# BrewPi_Fuscus_Board.net
KiCad netlist of a schematic drawn in EAGLE
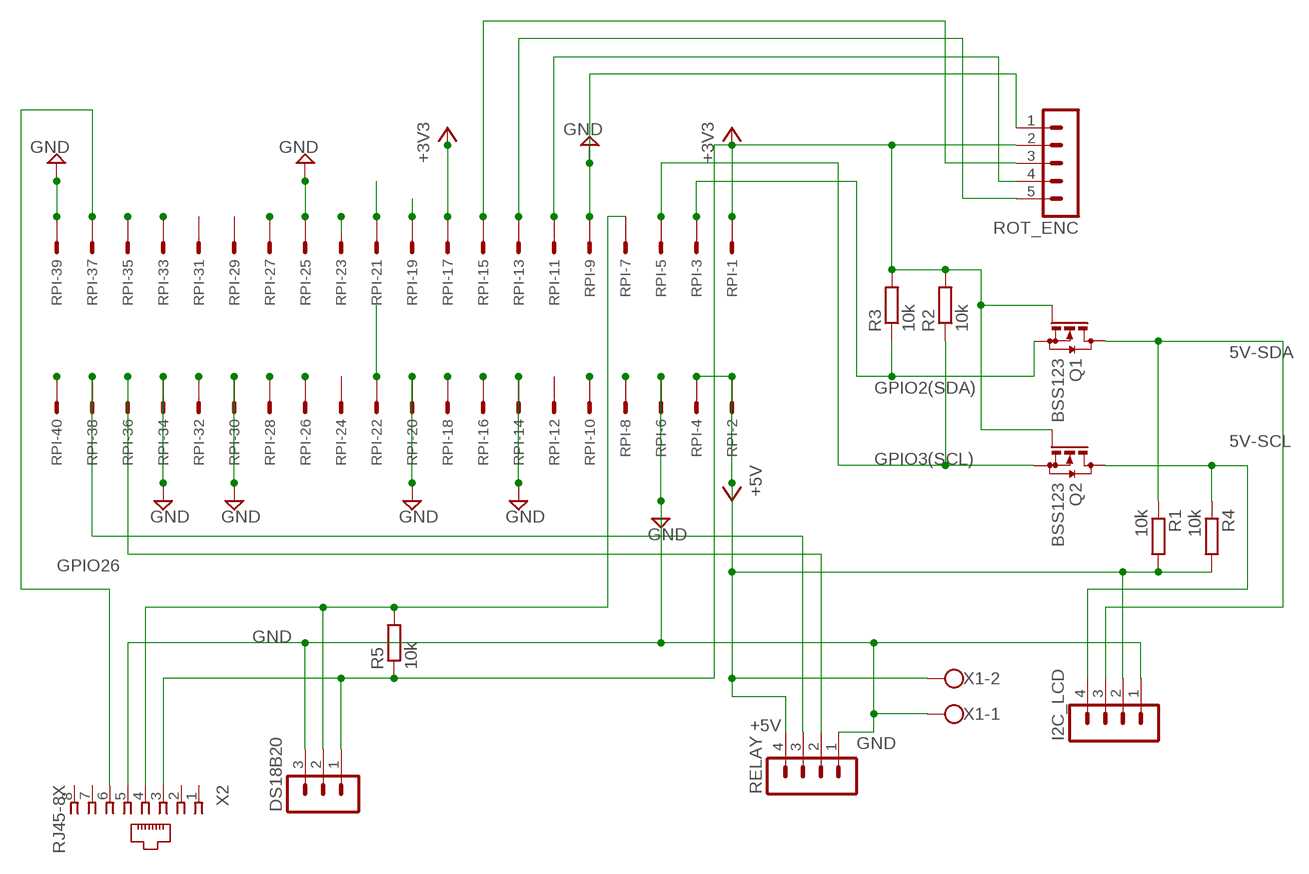
[diagram p0: schematic, sheet 1]

(export (version "E")
  (design (tool "Eeschema 10.0.6"))
  (components
    (comp (ref "DS18B20")
      (value "MA03-1")
      (footprint "eagle-import:MA03-1")
      (libsource (lib "eagle-import") (part "MA03-1"))
    )
    (comp (ref "I2C_LCD")
      (value "MA04-1")
      (footprint "eagle-import:MA04-1")
      (libsource (lib "eagle-import") (part "MA04-1"))
    )
    (comp (ref "Q1")
      (value "BSS123")
      (footprint "eagle-import:SOT23")
      (libsource (lib "eagle-import") (part "BSS123"))
    )
    (comp (ref "Q2")
      (value "BSS123")
      (footprint "eagle-import:SOT23")
      (libsource (lib "eagle-import") (part "BSS123"))
    )
    (comp (ref "R1")
      (value "10k")
      (footprint "eagle-import:M1206")
      (libsource (lib "eagle-import") (part "R-EU_M1206"))
    )
    (comp (ref "R2")
      (value "10k")
      (footprint "eagle-import:M1206")
      (libsource (lib "eagle-import") (part "R-EU_M1206"))
    )
    (comp (ref "R3")
      (value "10k")
      (footprint "eagle-import:M1206")
      (libsource (lib "eagle-import") (part "R-EU_M1206"))
    )
    (comp (ref "R4")
      (value "10k")
      (footprint "eagle-import:M1206")
      (libsource (lib "eagle-import") (part "R-EU_M1206"))
    )
    (comp (ref "R5")
      (value "10k")
      (footprint "eagle-import:M1206")
      (libsource (lib "eagle-import") (part "R-EU_M1206"))
    )
    (comp (ref "RELAY")
      (value "MA04-1")
      (footprint "eagle-import:MA04-1")
      (libsource (lib "eagle-import") (part "MA04-1"))
    )
    (comp (ref "ROT_ENC")
      (value "MA05-1")
      (footprint "eagle-import:MA05-1")
      (libsource (lib "eagle-import") (part "MA05-1"))
    )
    (comp (ref "RPI")
      (value "057-040-1")
      (footprint "eagle-import:057-040-1")
      (libsource (lib "eagle-import") (part "057-040-1"))
    )
    (comp (ref "X1")
      (value "W237-102")
      (footprint "eagle-import:W237-102")
      (fields (field (name "MPN") "237-102"))
      (libsource (lib "eagle-import") (part "W237-102"))
    )
    (comp (ref "X2")
      (value "RJ45-8X")
      (footprint "eagle-import:RJ45-NO-SHIELD")
      (libsource (lib "eagle-import") (part "RJ45-8X"))
    )
  )
  (nets
    (net (code "1") (name "+3V3") (class "Default")
      (node (ref "DS18B20") (pin "1") (pinfunction "1_1") (pintype "passive"))
      (node (ref "Q1") (pin "1") (pinfunction "G_1") (pintype "passive"))
      (node (ref "Q2") (pin "1") (pinfunction "G_1") (pintype "passive"))
      (node (ref "R2") (pin "2") (pinfunction "2_2") (pintype "passive"))
      (node (ref "R3") (pin "2") (pinfunction "2_2") (pintype "passive"))
      (node (ref "R5") (pin "1") (pinfunction "1_1") (pintype "passive"))
      (node (ref "ROT_ENC") (pin "2") (pinfunction "2_2") (pintype "passive"))
      (node (ref "RPI") (pin "1") (pinfunction "S_1") (pintype "passive"))
      (node (ref "RPI") (pin "17") (pinfunction "S_17") (pintype "passive"))
      (node (ref "X2") (pin "3") (pinfunction "3_3") (pintype "passive"))
    )
    (net (code "2") (name "+5V") (class "Default")
      (node (ref "I2C_LCD") (pin "2") (pinfunction "2_2") (pintype "passive"))
      (node (ref "R1") (pin "2") (pinfunction "2_2") (pintype "passive"))
      (node (ref "R4") (pin "2") (pinfunction "2_2") (pintype "passive"))
      (node (ref "RELAY") (pin "4") (pinfunction "4_4") (pintype "passive"))
      (node (ref "RPI") (pin "2") (pinfunction "S_2") (pintype "passive"))
      (node (ref "RPI") (pin "4") (pinfunction "S_4") (pintype "passive"))
      (node (ref "X1") (pin "2") (pinfunction "KL_2") (pintype "passive"))
    )
    (net (code "3") (name "/5V-SCL") (class "Default")
      (node (ref "I2C_LCD") (pin "4") (pinfunction "4_4") (pintype "passive"))
      (node (ref "Q2") (pin "3") (pinfunction "D_3") (pintype "passive"))
      (node (ref "R4") (pin "1") (pinfunction "1_1") (pintype "passive"))
    )
    (net (code "4") (name "/5V-SDA") (class "Default")
      (node (ref "I2C_LCD") (pin "3") (pinfunction "3_3") (pintype "passive"))
      (node (ref "Q1") (pin "3") (pinfunction "D_3") (pintype "passive"))
      (node (ref "R1") (pin "1") (pinfunction "1_1") (pintype "passive"))
    )
    (net (code "5") (name "/GPIO2(SDA)") (class "Default")
      (node (ref "Q1") (pin "2") (pinfunction "S_2") (pintype "passive"))
      (node (ref "R3") (pin "1") (pinfunction "1_1") (pintype "passive"))
      (node (ref "RPI") (pin "3") (pinfunction "S_3") (pintype "passive"))
    )
    (net (code "6") (name "/GPIO3(SCL)") (class "Default")
      (node (ref "Q2") (pin "2") (pinfunction "S_2") (pintype "passive"))
      (node (ref "R2") (pin "1") (pinfunction "1_1") (pintype "passive"))
      (node (ref "RPI") (pin "5") (pinfunction "S_5") (pintype "passive"))
    )
    (net (code "7") (name "/GPIO26") (class "Default")
      (node (ref "RPI") (pin "37") (pinfunction "S_37") (pintype "passive"))
      (node (ref "X2") (pin "6") (pinfunction "6_6") (pintype "passive"))
    )
    (net (code "8") (name "GND") (class "Default")
      (node (ref "DS18B20") (pin "3") (pinfunction "3_3") (pintype "passive"))
      (node (ref "I2C_LCD") (pin "1") (pinfunction "1_1") (pintype "passive"))
      (node (ref "RELAY") (pin "1") (pinfunction "1_1") (pintype "passive"))
      (node (ref "ROT_ENC") (pin "1") (pinfunction "1_1") (pintype "passive"))
      (node (ref "RPI") (pin "14") (pinfunction "S_14") (pintype "passive"))
      (node (ref "RPI") (pin "20") (pinfunction "S_20") (pintype "passive"))
      (node (ref "RPI") (pin "25") (pinfunction "S_25") (pintype "passive"))
      (node (ref "RPI") (pin "30") (pinfunction "S_30") (pintype "passive"))
      (node (ref "RPI") (pin "34") (pinfunction "S_34") (pintype "passive"))
      (node (ref "RPI") (pin "39") (pinfunction "S_39") (pintype "passive"))
      (node (ref "RPI") (pin "6") (pinfunction "S_6") (pintype "passive"))
      (node (ref "RPI") (pin "9") (pinfunction "S_9") (pintype "passive"))
      (node (ref "X1") (pin "1") (pinfunction "KL_1") (pintype "passive"))
      (node (ref "X2") (pin "5") (pinfunction "5_5") (pintype "passive"))
    )
    (net (code "9") (name "Net-(RPIAD-S)") (class "Default")
      (node (ref "RELAY") (pin "2") (pinfunction "2_2") (pintype "passive"))
      (node (ref "RPI") (pin "36") (pinfunction "S_36") (pintype "passive"))
    )
    (net (code "10") (name "Net-(RPIAF-S)") (class "Default")
      (node (ref "RELAY") (pin "3") (pinfunction "3_3") (pintype "passive"))
      (node (ref "RPI") (pin "38") (pinfunction "S_38") (pintype "passive"))
    )
    (net (code "11") (name "Net-(RPIAL-S)") (class "Default")
      (node (ref "DS18B20") (pin "2") (pinfunction "2_2") (pintype "passive"))
      (node (ref "R5") (pin "2") (pinfunction "2_2") (pintype "passive"))
      (node (ref "RPI") (pin "7") (pinfunction "S_7") (pintype "passive"))
      (node (ref "X2") (pin "4") (pinfunction "4_4") (pintype "passive"))
    )
    (net (code "12") (name "Net-(RPIC-S)") (class "Default")
      (node (ref "ROT_ENC") (pin "4") (pinfunction "4_4") (pintype "passive"))
      (node (ref "RPI") (pin "11") (pinfunction "S_11") (pintype "passive"))
    )
    (net (code "13") (name "Net-(RPIE-S)") (class "Default")
      (node (ref "ROT_ENC") (pin "5") (pinfunction "5_5") (pintype "passive"))
      (node (ref "RPI") (pin "13") (pinfunction "S_13") (pintype "passive"))
    )
    (net (code "14") (name "Net-(RPIG-S)") (class "Default")
      (node (ref "ROT_ENC") (pin "3") (pinfunction "3_3") (pintype "passive"))
      (node (ref "RPI") (pin "15") (pinfunction "S_15") (pintype "passive"))
    )
    (net (code "15") (name "unconnected-(RPIAA-S-Pad33)") (class "Default")
      (node (ref "RPI") (pin "33") (pinfunction "S_33") (pintype "passive"))
    )
    (net (code "16") (name "unconnected-(RPIAC-S-Pad35)") (class "Default")
      (node (ref "RPI") (pin "35") (pinfunction "S_35") (pintype "passive"))
    )
    (net (code "17") (name "unconnected-(RPIAI-S-Pad40)") (class "Default")
      (node (ref "RPI") (pin "40") (pinfunction "S_40") (pintype "passive"))
    )
    (net (code "18") (name "unconnected-(RPIAM-S-Pad8)") (class "Default")
      (node (ref "RPI") (pin "8") (pinfunction "S_8") (pintype "passive"))
    )
    (net (code "19") (name "unconnected-(RPIB-S-Pad10)") (class "Default")
      (node (ref "RPI") (pin "10") (pinfunction "S_10") (pintype "passive"))
    )
    (net (code "20") (name "unconnected-(RPID-S-Pad12)") (class "Default")
      (node (ref "RPI") (pin "12") (pinfunction "S_12") (pintype "passive"))
    )
    (net (code "21") (name "unconnected-(RPIH-S-Pad16)") (class "Default")
      (node (ref "RPI") (pin "16") (pinfunction "S_16") (pintype "passive"))
    )
    (net (code "22") (name "unconnected-(RPIJ-S-Pad18)") (class "Default")
      (node (ref "RPI") (pin "18") (pinfunction "S_18") (pintype "passive"))
    )
    (net (code "23") (name "unconnected-(RPIK-S-Pad19)") (class "Default")
      (node (ref "RPI") (pin "19") (pinfunction "S_19") (pintype "passive"))
    )
    (net (code "24") (name "unconnected-(RPIN-S-Pad21)") (class "Default")
      (node (ref "RPI") (pin "21") (pinfunction "S_21") (pintype "passive"))
    )
    (net (code "25") (name "unconnected-(RPIO-S-Pad22)") (class "Default")
      (node (ref "RPI") (pin "22") (pinfunction "S_22") (pintype "passive"))
    )
    (net (code "26") (name "unconnected-(RPIP-S-Pad23)") (class "Default")
      (node (ref "RPI") (pin "23") (pinfunction "S_23") (pintype "passive"))
    )
    (net (code "27") (name "unconnected-(RPIQ-S-Pad24)") (class "Default")
      (node (ref "RPI") (pin "24") (pinfunction "S_24") (pintype "passive"))
    )
    (net (code "28") (name "unconnected-(RPIS-S-Pad26)") (class "Default")
      (node (ref "RPI") (pin "26") (pinfunction "S_26") (pintype "passive"))
    )
    (net (code "29") (name "unconnected-(RPIT-S-Pad27)") (class "Default")
      (node (ref "RPI") (pin "27") (pinfunction "S_27") (pintype "passive"))
    )
    (net (code "30") (name "unconnected-(RPIU-S-Pad28)") (class "Default")
      (node (ref "RPI") (pin "28") (pinfunction "S_28") (pintype "passive"))
    )
    (net (code "31") (name "unconnected-(RPIV-S-Pad29)") (class "Default")
      (node (ref "RPI") (pin "29") (pinfunction "S_29") (pintype "passive"))
    )
    (net (code "32") (name "unconnected-(RPIY-S-Pad31)") (class "Default")
      (node (ref "RPI") (pin "31") (pinfunction "S_31") (pintype "passive"))
    )
    (net (code "33") (name "unconnected-(RPIZ-S-Pad32)") (class "Default")
      (node (ref "RPI") (pin "32") (pinfunction "S_32") (pintype "passive"))
    )
    (net (code "34") (name "unconnected-(X2-Pad1)") (class "Default")
      (node (ref "X2") (pin "1") (pinfunction "1_1") (pintype "passive"))
    )
    (net (code "35") (name "unconnected-(X2-Pad2)") (class "Default")
      (node (ref "X2") (pin "2") (pinfunction "2_2") (pintype "passive"))
    )
    (net (code "36") (name "unconnected-(X2-Pad7)") (class "Default")
      (node (ref "X2") (pin "7") (pinfunction "7_7") (pintype "passive"))
    )
    (net (code "37") (name "unconnected-(X2-Pad8)") (class "Default")
      (node (ref "X2") (pin "8") (pinfunction "8_8") (pintype "passive"))
    )
  )
)
